# Connectors.net
KiCad netlist of a schematic drawn in Altium Designer
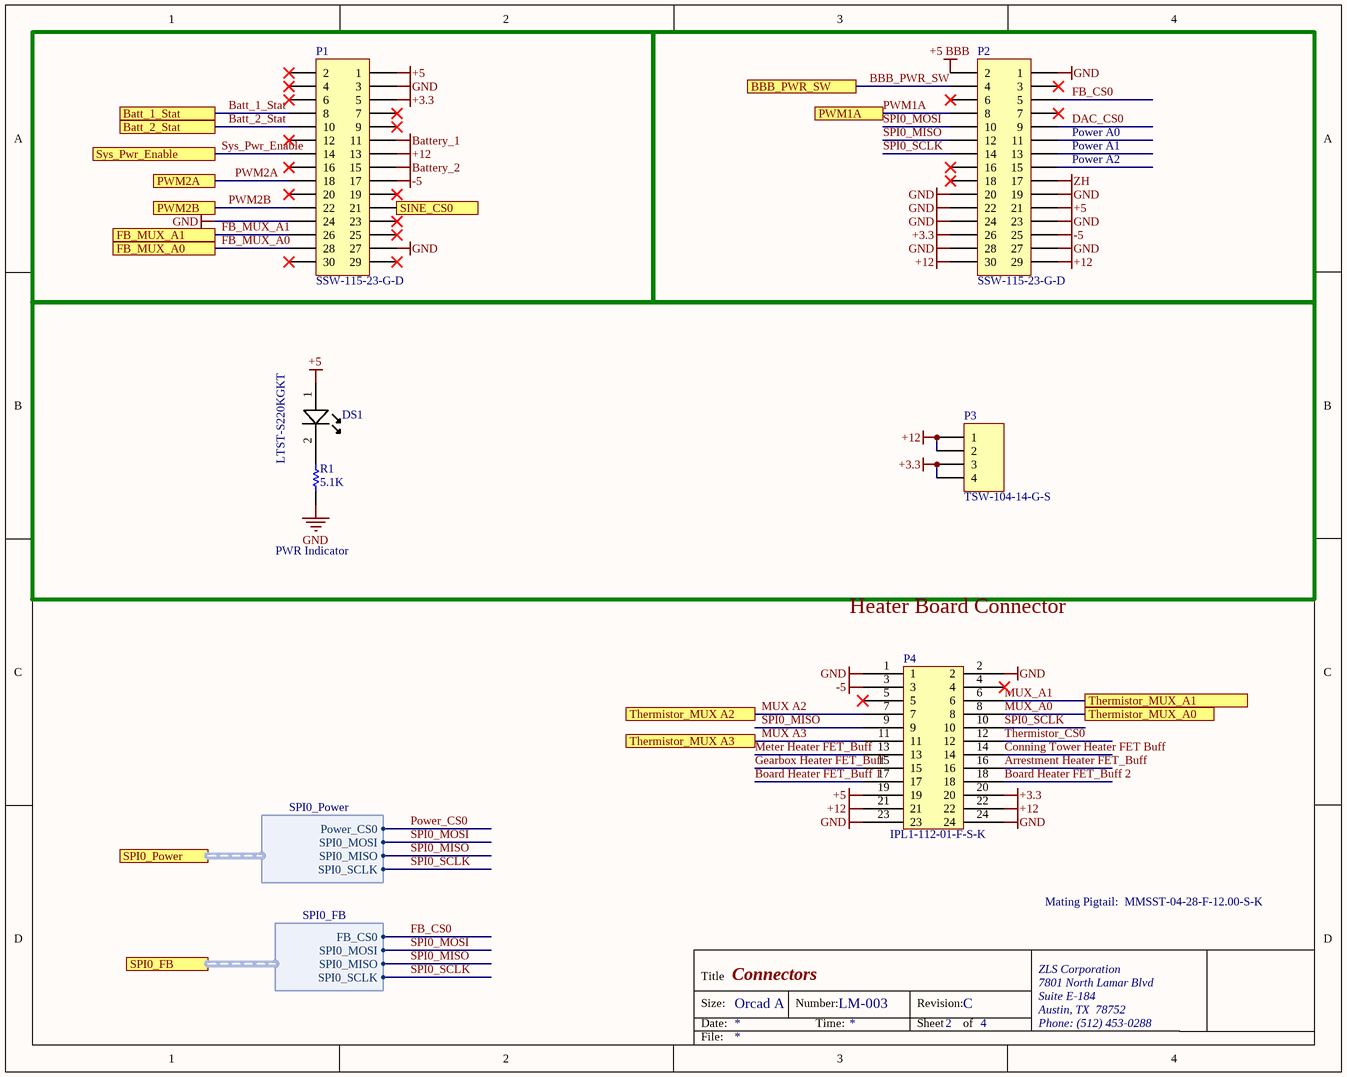
[diagram p0: Connectors.SchDoc]

(export (version "E")
  (design (tool "Eeschema 10.0.6"))
  (components
    (comp (ref "DS1")
      (value "Lite-On LTST-S220KGKT Green LED, 571 nm 2012 (0805) Side View, Rectangle Lens SMD package")
      (footprint "0805C_L")
      (fields
        (field (name "MANUFACTURER") "Vishay / Lite-On")
        (field (name "MANUFACTURER PART NUMBER") "LTST-S220KGKT")
      )
      (libsource (lib "*") (part "LED A/K"))
    )
    (comp (ref "P1")
      (value "SSW-115-23-G-D")
      (footprint "SSW-115-23-G-D")
      (description "Header, 15-Pin, Dual row")
      (fields (field (name "MANUFACTURER") "Samtec Inc."))
      (libsource (lib "Miscellaneous Connectors") (part "Header 15X2"))
    )
    (comp (ref "P2")
      (value "SSW-115-23-G-D")
      (footprint "SSW-115-23-G-D")
      (description "Header, 15-Pin, Dual row")
      (fields (field (name "MANUFACTURER") "Samtec Inc."))
      (libsource (lib "Miscellaneous Connectors") (part "Header 15X2"))
    )
    (comp (ref "P3")
      (value "TSW-104-14-G-S")
      (footprint "HDR1X4")
      (description "Header, 4-Pin")
      (fields (field (name "MANUFACTURER") "Samtec Inc."))
      (libsource (lib "Miscellaneous Connectors") (part "Header 4"))
    )
    (comp (ref "P4")
      (value "IPL1-112-01-F-S-K")
      (footprint "IPL1-112-01-F-S-K")
      (description "IPL1-112-01-F-D-K")
      (fields (field (name "MANUFACTURER") "Samtec Inc."))
      (libsource (lib "ZLS_Schematic_lib") (part "IPL1-112-01-F-S-K"))
    )
    (comp (ref "R1")
      (value "5.1K")
      (footprint "RESC0805(2012)_L")
      (description "RES SMD 5.1K OHM 5% 1/8W 0805")
      (fields
        (field (name "MANUFACTURER") "Vishay Dale")
        (field (name "MANUFACTURER PART NUMBER") "CRCW08055K10JNEA")
      )
      (libsource (lib "Altium Content Vault") (part "CMP-1013-00215-1"))
    )
  )
  (nets
    (net (code "3") (name "+3.3") (class "Default")
      (node (ref "P1") (pin "5") (pinfunction "5_5") (pintype "passive"))
      (node (ref "P2") (pin "26") (pinfunction "26_26") (pintype "passive"))
      (node (ref "P3") (pin "3") (pinfunction "3_3") (pintype "passive"))
      (node (ref "P3") (pin "4") (pinfunction "4_4") (pintype "passive"))
      (node (ref "P4") (pin "20") (pinfunction "20_20") (pintype "passive"))
    )
    (net (code "4") (name "+5") (class "Default")
      (node (ref "DS1") (pin "1") (pinfunction "A_1") (pintype "passive"))
      (node (ref "P1") (pin "1") (pinfunction "1_1") (pintype "passive"))
      (node (ref "P2") (pin "21") (pinfunction "21_21") (pintype "passive"))
      (node (ref "P4") (pin "19") (pinfunction "19_19") (pintype "passive"))
    )
    (net (code "5") (name "+5 BBB") (class "Default")
      (node (ref "P2") (pin "2") (pinfunction "2_2") (pintype "passive"))
    )
    (net (code "6") (name "+12") (class "Default")
      (node (ref "P1") (pin "13") (pinfunction "13_13") (pintype "passive"))
      (node (ref "P2") (pin "29") (pinfunction "29_29") (pintype "passive"))
      (node (ref "P2") (pin "30") (pinfunction "30_30") (pintype "passive"))
      (node (ref "P3") (pin "1") (pinfunction "1_1") (pintype "passive"))
      (node (ref "P3") (pin "2") (pinfunction "2_2") (pintype "passive"))
      (node (ref "P4") (pin "21") (pinfunction "21_21") (pintype "passive"))
      (node (ref "P4") (pin "22") (pinfunction "22_22") (pintype "passive"))
    )
    (net (code "7") (name "-5") (class "Default")
      (node (ref "P1") (pin "17") (pinfunction "17_17") (pintype "passive"))
      (node (ref "P2") (pin "25") (pinfunction "25_25") (pintype "passive"))
      (node (ref "P4") (pin "3") (pinfunction "3_3") (pintype "passive"))
    )
    (net (code "8") (name "/Arrestment Heater FET_Buff") (class "Default")
      (node (ref "P4") (pin "16") (pinfunction "16_16") (pintype "passive"))
    )
    (net (code "9") (name "/BBB_PWR_SW") (class "Default")
      (node (ref "P2") (pin "4") (pinfunction "4_4") (pintype "passive"))
    )
    (net (code "10") (name "/Batt_1_Stat") (class "Default")
      (node (ref "P1") (pin "8") (pinfunction "8_8") (pintype "passive"))
    )
    (net (code "11") (name "/Batt_2_Stat") (class "Default")
      (node (ref "P1") (pin "10") (pinfunction "10_10") (pintype "passive"))
    )
    (net (code "12") (name "/Board Heater FET_Buff 1") (class "Default")
      (node (ref "P4") (pin "17") (pinfunction "17_17") (pintype "passive"))
    )
    (net (code "13") (name "/Board Heater FET_Buff 2") (class "Default")
      (node (ref "P4") (pin "18") (pinfunction "18_18") (pintype "passive"))
    )
    (net (code "14") (name "/Conning Tower Heater FET Buff") (class "Default")
      (node (ref "P4") (pin "14") (pinfunction "14_14") (pintype "passive"))
    )
    (net (code "15") (name "/DAC_CS0") (class "Default")
      (node (ref "P2") (pin "9") (pinfunction "9_9") (pintype "passive"))
    )
    (net (code "16") (name "/FB_CS0") (class "Default")
      (node (ref "P2") (pin "5") (pinfunction "5_5") (pintype "passive"))
    )
    (net (code "17") (name "/FB_MUX_A0") (class "Default")
      (node (ref "P1") (pin "28") (pinfunction "28_28") (pintype "passive"))
    )
    (net (code "18") (name "/FB_MUX_A1") (class "Default")
      (node (ref "P1") (pin "26") (pinfunction "26_26") (pintype "passive"))
    )
    (net (code "19") (name "/Gearbox Heater FET_Buff") (class "Default")
      (node (ref "P4") (pin "15") (pinfunction "15_15") (pintype "passive"))
    )
    (net (code "20") (name "/MUX A2") (class "Default")
      (node (ref "P4") (pin "7") (pinfunction "7_7") (pintype "passive"))
    )
    (net (code "21") (name "/MUX A3") (class "Default")
      (node (ref "P4") (pin "11") (pinfunction "11_11") (pintype "passive"))
    )
    (net (code "22") (name "/MUX_A0") (class "Default")
      (node (ref "P4") (pin "8") (pinfunction "8_8") (pintype "passive"))
    )
    (net (code "23") (name "/MUX_A1") (class "Default")
      (node (ref "P4") (pin "6") (pinfunction "6_6") (pintype "passive"))
    )
    (net (code "24") (name "/Meter Heater FET_Buff") (class "Default")
      (node (ref "P4") (pin "13") (pinfunction "13_13") (pintype "passive"))
    )
    (net (code "25") (name "/PWM1A") (class "Default")
      (node (ref "P2") (pin "8") (pinfunction "8_8") (pintype "passive"))
    )
    (net (code "26") (name "/PWM2A") (class "Default")
      (node (ref "P1") (pin "18") (pinfunction "18_18") (pintype "passive"))
    )
    (net (code "27") (name "/PWM2B") (class "Default")
      (node (ref "P1") (pin "22") (pinfunction "22_22") (pintype "passive"))
    )
    (net (code "29") (name "/SINE_CS0") (class "Default")
      (node (ref "P1") (pin "21") (pinfunction "21_21") (pintype "passive"))
    )
    (net (code "30") (name "/SPI0_MISO") (class "Default")
      (node (ref "P2") (pin "12") (pinfunction "12_12") (pintype "passive"))
      (node (ref "P4") (pin "9") (pinfunction "9_9") (pintype "passive"))
    )
    (net (code "31") (name "/SPI0_MOSI") (class "Default")
      (node (ref "P2") (pin "10") (pinfunction "10_10") (pintype "passive"))
    )
    (net (code "32") (name "/SPI0_SCLK") (class "Default")
      (node (ref "P2") (pin "14") (pinfunction "14_14") (pintype "passive"))
      (node (ref "P4") (pin "10") (pinfunction "10_10") (pintype "passive"))
    )
    (net (code "33") (name "/Sys_Pwr_Enable") (class "Default")
      (node (ref "P1") (pin "14") (pinfunction "14_14") (pintype "passive"))
    )
    (net (code "34") (name "/Thermistor_CS0") (class "Default")
      (node (ref "P4") (pin "12") (pinfunction "12_12") (pintype "passive"))
    )
    (net (code "37") (name "Battery_1") (class "Default")
      (node (ref "P1") (pin "11") (pinfunction "11_11") (pintype "passive"))
    )
    (net (code "38") (name "Battery_2") (class "Default")
      (node (ref "P1") (pin "15") (pinfunction "15_15") (pintype "passive"))
    )
    (net (code "39") (name "GND") (class "Default")
      (node (ref "P1") (pin "24") (pinfunction "24_24") (pintype "passive"))
      (node (ref "P1") (pin "27") (pinfunction "27_27") (pintype "passive"))
      (node (ref "P1") (pin "3") (pinfunction "3_3") (pintype "passive"))
      (node (ref "P2") (pin "1") (pinfunction "1_1") (pintype "passive"))
      (node (ref "P2") (pin "19") (pinfunction "19_19") (pintype "passive"))
      (node (ref "P2") (pin "20") (pinfunction "20_20") (pintype "passive"))
      (node (ref "P2") (pin "22") (pinfunction "22_22") (pintype "passive"))
      (node (ref "P2") (pin "23") (pinfunction "23_23") (pintype "passive"))
      (node (ref "P2") (pin "24") (pinfunction "24_24") (pintype "passive"))
      (node (ref "P2") (pin "27") (pinfunction "27_27") (pintype "passive"))
      (node (ref "P2") (pin "28") (pinfunction "28_28") (pintype "passive"))
      (node (ref "P4") (pin "1") (pinfunction "1_1") (pintype "passive"))
      (node (ref "P4") (pin "2") (pinfunction "2_2") (pintype "passive"))
      (node (ref "P4") (pin "23") (pinfunction "23_23") (pintype "passive"))
      (node (ref "P4") (pin "24") (pinfunction "24_24") (pintype "passive"))
      (node (ref "R1") (pin "2") (pinfunction "2_2") (pintype "passive"))
    )
    (net (code "40") (name "Net-(DS1-K)") (class "Default")
      (node (ref "DS1") (pin "2") (pinfunction "K_2") (pintype "passive"))
      (node (ref "R1") (pin "1") (pinfunction "1_1") (pintype "passive"))
    )
    (net (code "41") (name "ZH") (class "Default")
      (node (ref "P2") (pin "17") (pinfunction "17_17") (pintype "passive"))
    )
    (net (code "42") (name "unconnected-(P1-Pad2)") (class "Default")
      (node (ref "P1") (pin "2") (pinfunction "2_2") (pintype "passive+no_connect"))
    )
    (net (code "43") (name "unconnected-(P1-Pad4)") (class "Default")
      (node (ref "P1") (pin "4") (pinfunction "4_4") (pintype "passive+no_connect"))
    )
    (net (code "44") (name "unconnected-(P1-Pad6)") (class "Default")
      (node (ref "P1") (pin "6") (pinfunction "6_6") (pintype "passive+no_connect"))
    )
    (net (code "45") (name "unconnected-(P1-Pad7)") (class "Default")
      (node (ref "P1") (pin "7") (pinfunction "7_7") (pintype "passive+no_connect"))
    )
    (net (code "46") (name "unconnected-(P1-Pad9)") (class "Default")
      (node (ref "P1") (pin "9") (pinfunction "9_9") (pintype "passive+no_connect"))
    )
    (net (code "47") (name "unconnected-(P1-Pad12)") (class "Default")
      (node (ref "P1") (pin "12") (pinfunction "12_12") (pintype "passive+no_connect"))
    )
    (net (code "48") (name "unconnected-(P1-Pad16)") (class "Default")
      (node (ref "P1") (pin "16") (pinfunction "16_16") (pintype "passive+no_connect"))
    )
    (net (code "49") (name "unconnected-(P1-Pad19)") (class "Default")
      (node (ref "P1") (pin "19") (pinfunction "19_19") (pintype "passive+no_connect"))
    )
    (net (code "50") (name "unconnected-(P1-Pad20)") (class "Default")
      (node (ref "P1") (pin "20") (pinfunction "20_20") (pintype "passive+no_connect"))
    )
    (net (code "51") (name "unconnected-(P1-Pad23)") (class "Default")
      (node (ref "P1") (pin "23") (pinfunction "23_23") (pintype "passive+no_connect"))
    )
    (net (code "52") (name "unconnected-(P1-Pad25)") (class "Default")
      (node (ref "P1") (pin "25") (pinfunction "25_25") (pintype "passive+no_connect"))
    )
    (net (code "53") (name "unconnected-(P1-Pad29)") (class "Default")
      (node (ref "P1") (pin "29") (pinfunction "29_29") (pintype "passive+no_connect"))
    )
    (net (code "54") (name "unconnected-(P1-Pad30)") (class "Default")
      (node (ref "P1") (pin "30") (pinfunction "30_30") (pintype "passive+no_connect"))
    )
    (net (code "55") (name "unconnected-(P2-Pad3)") (class "Default")
      (node (ref "P2") (pin "3") (pinfunction "3_3") (pintype "passive+no_connect"))
    )
    (net (code "56") (name "unconnected-(P2-Pad6)") (class "Default")
      (node (ref "P2") (pin "6") (pinfunction "6_6") (pintype "passive+no_connect"))
    )
    (net (code "57") (name "unconnected-(P2-Pad7)") (class "Default")
      (node (ref "P2") (pin "7") (pinfunction "7_7") (pintype "passive+no_connect"))
    )
    (net (code "58") (name "unconnected-(P2-Pad11)") (class "Default")
      (node (ref "P2") (pin "11") (pinfunction "11_11") (pintype "passive"))
    )
    (net (code "59") (name "unconnected-(P2-Pad13)") (class "Default")
      (node (ref "P2") (pin "13") (pinfunction "13_13") (pintype "passive"))
    )
    (net (code "60") (name "unconnected-(P2-Pad15)") (class "Default")
      (node (ref "P2") (pin "15") (pinfunction "15_15") (pintype "passive"))
    )
    (net (code "61") (name "unconnected-(P2-Pad16)") (class "Default")
      (node (ref "P2") (pin "16") (pinfunction "16_16") (pintype "passive+no_connect"))
    )
    (net (code "62") (name "unconnected-(P2-Pad18)") (class "Default")
      (node (ref "P2") (pin "18") (pinfunction "18_18") (pintype "passive+no_connect"))
    )
    (net (code "63") (name "unconnected-(P4-Pad4)") (class "Default")
      (node (ref "P4") (pin "4") (pinfunction "4_4") (pintype "passive+no_connect"))
    )
    (net (code "64") (name "unconnected-(P4-Pad5)") (class "Default")
      (node (ref "P4") (pin "5") (pinfunction "5_5") (pintype "passive+no_connect"))
    )
  )
)
